# drv.net
KiCad netlist of a schematic drawn in Altium Designer
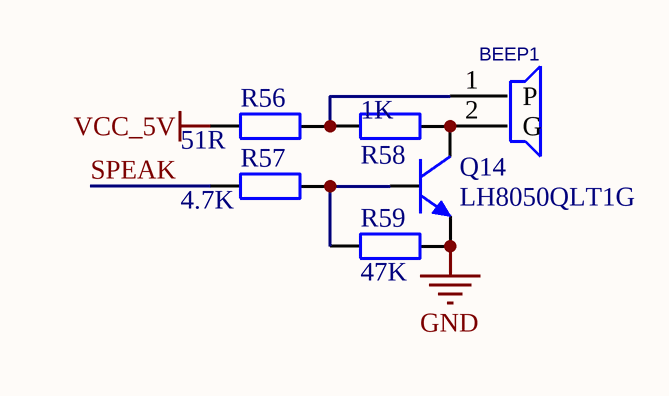
[diagram p0: drv.SchDoc]

(export (version "E")
  (design (tool "Eeschema 10.0.6"))
  (components
    (comp (ref "BEEP1")
      (value "BEEP-9.5X5.5")
      (footprint "BEEP-9.5X5.5")
      (libsource (lib "MINI-V3") (part "BEEP-9.5X5.5"))
    )
    (comp (ref "Q14")
      (value "LH8050QLT1G")
      (footprint "SOT-23")
      (description "NPN")
      (libsource (lib "XiaoyI") (part "NPN-1"))
    )
    (comp (ref "R56")
      (value "51R")
      (footprint "0603R")
      (description "贴片电阻 5%")
      (libsource (lib "") (part "RES0_1"))
    )
    (comp (ref "R57")
      (value "4.7K")
      (footprint "0603R")
      (description "贴片电阻 5%")
      (libsource (lib "ABB") (part "RES0"))
    )
    (comp (ref "R58")
      (value "1K")
      (footprint "0603R")
      (description "贴片电阻 5%")
      (libsource (lib "") (part "RES0_1"))
    )
    (comp (ref "R59")
      (value "47K")
      (footprint "0603R")
      (description "贴片电阻 5%")
      (libsource (lib "ABB") (part "RES0"))
    )
  )
  (nets
    (net (code "1") (name "/SPEAK") (class "Default")
      (node (ref "R57") (pin "1") (pinfunction "1_1") (pintype "passive"))
    )
    (net (code "2") (name "GND") (class "Default")
      (node (ref "Q14") (pin "2") (pinfunction "E_2") (pintype "passive"))
      (node (ref "R59") (pin "2") (pinfunction "2_2") (pintype "passive"))
    )
    (net (code "3") (name "Net-(BEEP1-G)") (class "Default")
      (node (ref "BEEP1") (pin "2") (pinfunction "G_2") (pintype "passive"))
      (node (ref "Q14") (pin "3") (pinfunction "C_3") (pintype "passive"))
      (node (ref "R58") (pin "1") (pinfunction "1_1") (pintype "passive"))
    )
    (net (code "4") (name "Net-(BEEP1-P)") (class "Default")
      (node (ref "BEEP1") (pin "1") (pinfunction "P_1") (pintype "passive"))
      (node (ref "R56") (pin "1") (pinfunction "1_1") (pintype "passive"))
      (node (ref "R58") (pin "2") (pinfunction "2_2") (pintype "passive"))
    )
    (net (code "5") (name "Net-(Q14-B)") (class "Default")
      (node (ref "Q14") (pin "1") (pinfunction "B_1") (pintype "passive"))
      (node (ref "R57") (pin "2") (pinfunction "2_2") (pintype "passive"))
      (node (ref "R59") (pin "1") (pinfunction "1_1") (pintype "passive"))
    )
    (net (code "6") (name "VCC_5V") (class "Default")
      (node (ref "R56") (pin "2") (pinfunction "2_2") (pintype "passive"))
    )
  )
)
